# ict_to_hid.net
KiCad netlist of a schematic drawn in EAGLE
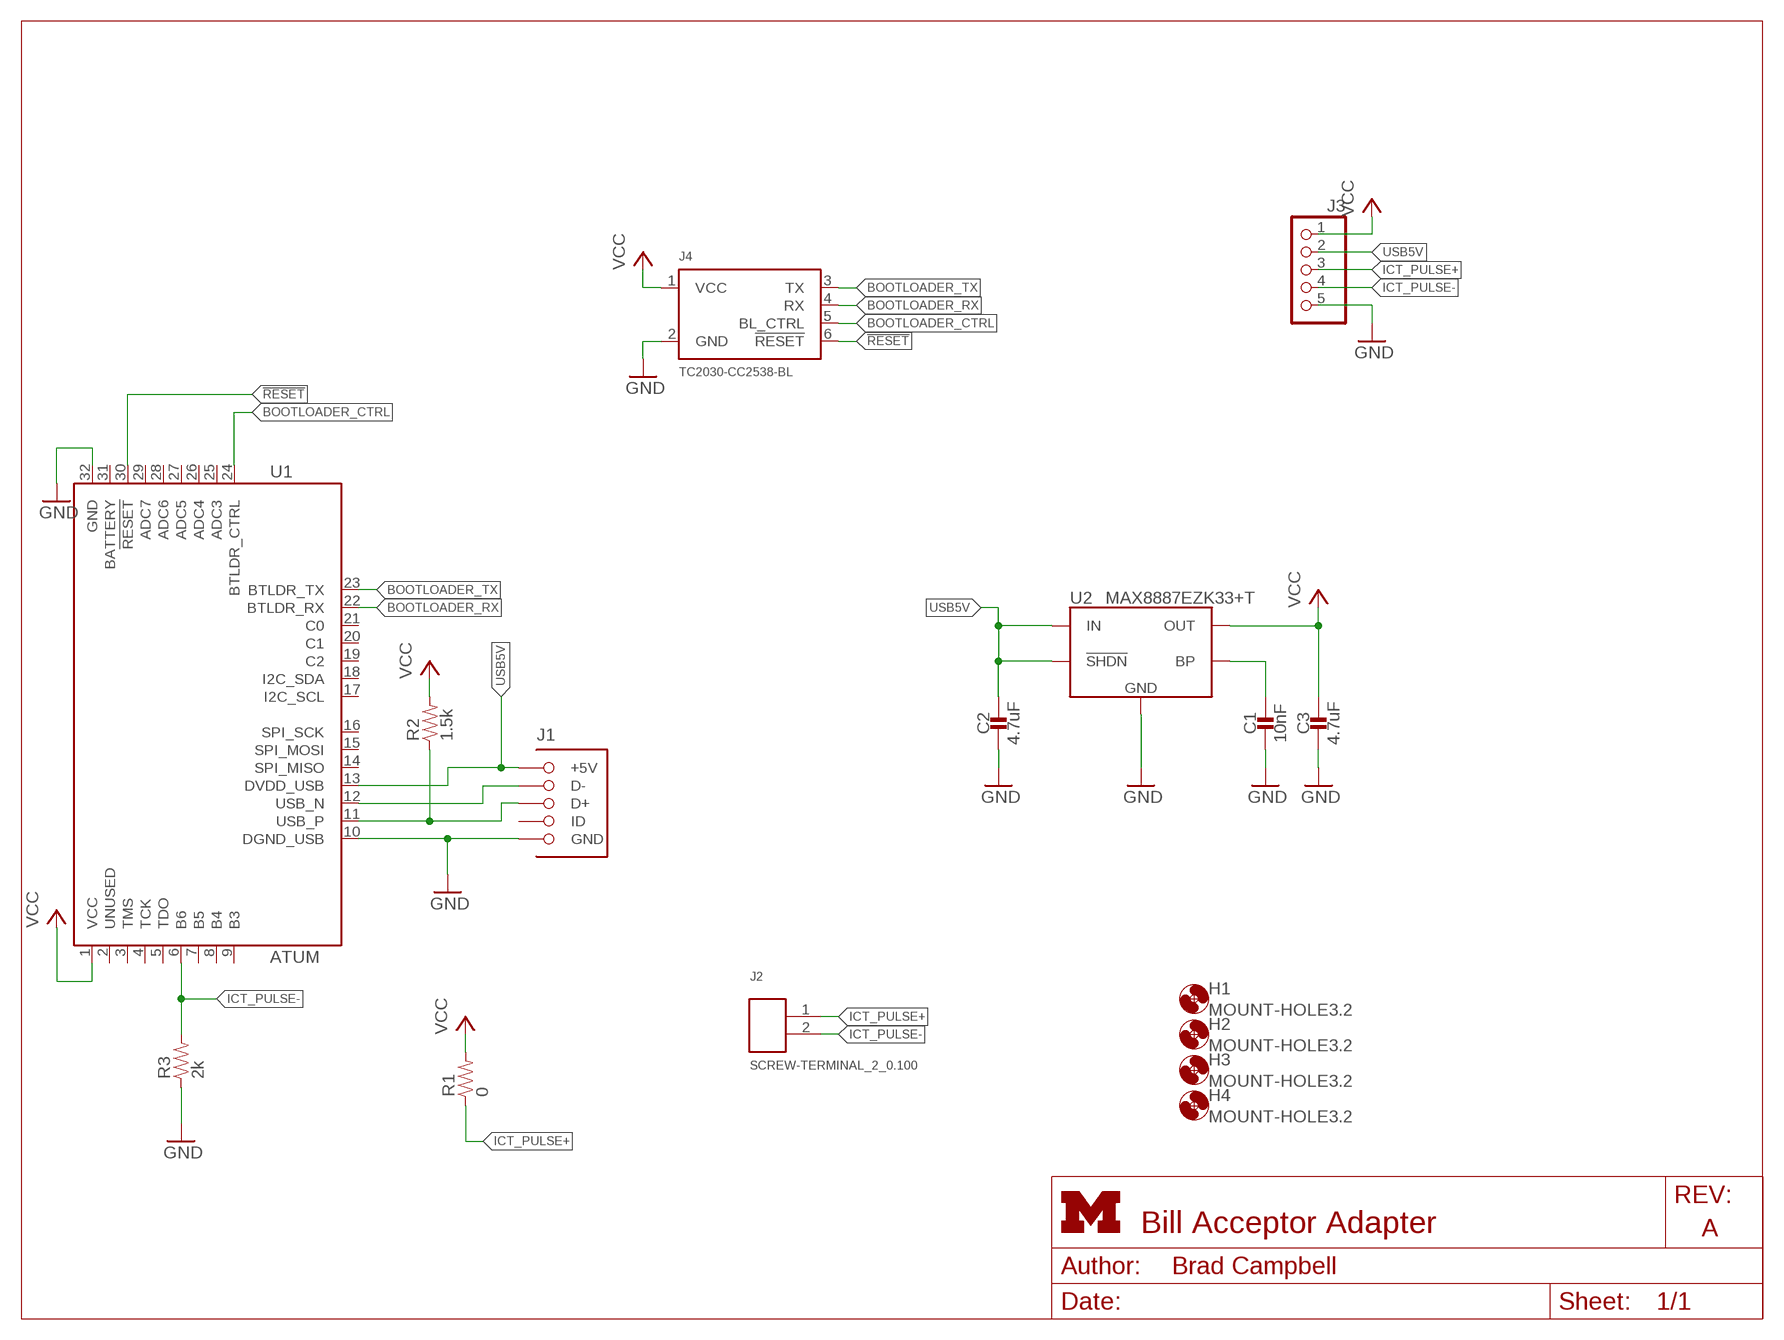
[diagram p0: schematic, sheet 1]

(export (version "E")
  (design (tool "Eeschema 10.0.6"))
  (components
    (comp (ref "C1")
      (value "10nF")
      (footprint "eagle-import:0603_CAP")
      (libsource (lib "eagle-import") (part "CAPACITOR0603_CAP"))
    )
    (comp (ref "C2")
      (value "4.7uF")
      (footprint "eagle-import:0603_CAP")
      (libsource (lib "eagle-import") (part "CAPACITOR0603_CAP"))
    )
    (comp (ref "C3")
      (value "4.7uF")
      (footprint "eagle-import:0603_CAP")
      (libsource (lib "eagle-import") (part "CAPACITOR0603_CAP"))
    )
    (comp (ref "H1")
      (value "MOUNT-HOLE3.2")
      (footprint "eagle-import:3,2")
      (libsource (lib "eagle-import") (part "MOUNT-HOLE3.2"))
    )
    (comp (ref "H2")
      (value "MOUNT-HOLE3.2")
      (footprint "eagle-import:3,2")
      (libsource (lib "eagle-import") (part "MOUNT-HOLE3.2"))
    )
    (comp (ref "H3")
      (value "MOUNT-HOLE3.2")
      (footprint "eagle-import:3,2")
      (libsource (lib "eagle-import") (part "MOUNT-HOLE3.2"))
    )
    (comp (ref "H4")
      (value "MOUNT-HOLE3.2")
      (footprint "eagle-import:3,2")
      (libsource (lib "eagle-import") (part "MOUNT-HOLE3.2"))
    )
    (comp (ref "J1")
      (value "MICRO_USB_B_HIROSE_ZX62R-B-5P")
      (footprint "eagle-import:USB_MICRO_B-HIROSE-ZX62R-B-5P")
      (libsource (lib "eagle-import") (part "MICRO_USB_B_HIROSE_ZX62R-B-5P"))
    )
    (comp (ref "J2")
      (value "SCREW-TERMINAL_2_0.100")
      (footprint "eagle-import:CONN_BLOCK_2")
      (libsource (lib "eagle-import") (part "SCREW-TERMINAL_2_0.100"))
    )
    (comp (ref "J3")
      (value "PINHD-1X5")
      (footprint "eagle-import:1X05")
      (libsource (lib "eagle-import") (part "PINHD-1X5"))
    )
    (comp (ref "J4")
      (value "TC2030-CC2538-BL")
      (footprint "eagle-import:TC2030-IDC")
      (libsource (lib "eagle-import") (part "TC2030-CC2538-BL"))
    )
    (comp (ref "R1")
      (value "0")
      (footprint "eagle-import:0603-RES")
      (libsource (lib "eagle-import") (part "RESISTOR0603_RES"))
    )
    (comp (ref "R2")
      (value "1.5k")
      (footprint "eagle-import:0603-RES")
      (libsource (lib "eagle-import") (part "RESISTOR0603_RES"))
    )
    (comp (ref "R3")
      (value "2k")
      (footprint "eagle-import:0603-RES")
      (libsource (lib "eagle-import") (part "RESISTOR0603_RES"))
    )
    (comp (ref "U1")
      (value "ATUM")
      (footprint "eagle-import:ATUM")
      (libsource (lib "eagle-import") (part "ATUM"))
    )
    (comp (ref "U2")
      (value "MAX8887EZK33+T")
      (footprint "eagle-import:SOT-23-5")
      (libsource (lib "eagle-import") (part "MAX8887EZK33+T"))
    )
  )
  (nets
    (net (code "1") (name "/~{RESET}") (class "Default")
      (node (ref "J4") (pin "6") (pinfunction "~{RESET}_6") (pintype "bidirectional"))
      (node (ref "U1") (pin "30") (pinfunction "~{RESET}_30") (pintype "bidirectional"))
    )
    (net (code "2") (name "BOOTLOADER_CTRL") (class "Default")
      (node (ref "J4") (pin "5") (pinfunction "BL_CTRL_5") (pintype "bidirectional"))
      (node (ref "U1") (pin "24") (pinfunction "BTLDR_CTRL_24") (pintype "bidirectional"))
    )
    (net (code "3") (name "BOOTLOADER_RX") (class "Default")
      (node (ref "J4") (pin "4") (pinfunction "RX_4") (pintype "bidirectional"))
      (node (ref "U1") (pin "22") (pinfunction "BTLDR_RX_22") (pintype "bidirectional"))
    )
    (net (code "4") (name "BOOTLOADER_TX") (class "Default")
      (node (ref "J4") (pin "3") (pinfunction "TX_3") (pintype "bidirectional"))
      (node (ref "U1") (pin "23") (pinfunction "BTLDR_TX_23") (pintype "bidirectional"))
    )
    (net (code "5") (name "GND") (class "Default")
      (node (ref "C1") (pin "2") (pinfunction "2_2") (pintype "bidirectional"))
      (node (ref "C2") (pin "2") (pinfunction "2_2") (pintype "bidirectional"))
      (node (ref "C3") (pin "2") (pinfunction "2_2") (pintype "bidirectional"))
      (node (ref "J1") (pin "5") (pinfunction "GND_5") (pintype "bidirectional"))
      (node (ref "J3") (pin "5") (pinfunction "5_5") (pintype "passive"))
      (node (ref "J4") (pin "2") (pinfunction "GND_2") (pintype "bidirectional"))
      (node (ref "R3") (pin "1") (pinfunction "1_1") (pintype "passive"))
      (node (ref "U1") (pin "10") (pinfunction "DGND_USB_10") (pintype "bidirectional"))
      (node (ref "U1") (pin "32") (pinfunction "GND_32") (pintype "bidirectional"))
      (node (ref "U2") (pin "2") (pinfunction "GND_2") (pintype "bidirectional"))
    )
    (net (code "6") (name "ICT_PULSE+") (class "Default")
      (node (ref "J2") (pin "1") (pinfunction "1_1") (pintype "bidirectional"))
      (node (ref "J3") (pin "3") (pinfunction "3_3") (pintype "passive"))
      (node (ref "R1") (pin "1") (pinfunction "1_1") (pintype "passive"))
    )
    (net (code "7") (name "ICT_PULSE-") (class "Default")
      (node (ref "J2") (pin "2") (pinfunction "2_2") (pintype "bidirectional"))
      (node (ref "J3") (pin "4") (pinfunction "4_4") (pintype "passive"))
      (node (ref "R3") (pin "2") (pinfunction "2_2") (pintype "passive"))
      (node (ref "U1") (pin "6") (pinfunction "B6_6") (pintype "bidirectional"))
    )
    (net (code "8") (name "Net-(J1-D+)") (class "Default")
      (node (ref "J1") (pin "3") (pinfunction "D+_3") (pintype "bidirectional"))
      (node (ref "R2") (pin "1") (pinfunction "1_1") (pintype "passive"))
      (node (ref "U1") (pin "11") (pinfunction "USB_P_11") (pintype "bidirectional"))
    )
    (net (code "9") (name "Net-(J1-D-)") (class "Default")
      (node (ref "J1") (pin "2") (pinfunction "D-_2") (pintype "bidirectional"))
      (node (ref "U1") (pin "12") (pinfunction "USB_N_12") (pintype "bidirectional"))
    )
    (net (code "10") (name "Net-(U2-BP)") (class "Default")
      (node (ref "C1") (pin "1") (pinfunction "1_1") (pintype "bidirectional"))
      (node (ref "U2") (pin "4") (pinfunction "BP_4") (pintype "bidirectional"))
    )
    (net (code "11") (name "USB5V") (class "Default")
      (node (ref "C2") (pin "1") (pinfunction "1_1") (pintype "bidirectional"))
      (node (ref "J1") (pin "1") (pinfunction "+5V_1") (pintype "bidirectional"))
      (node (ref "J3") (pin "2") (pinfunction "2_2") (pintype "passive"))
      (node (ref "U1") (pin "13") (pinfunction "DVDD_USB_13") (pintype "bidirectional"))
      (node (ref "U2") (pin "1") (pinfunction "IN_1") (pintype "bidirectional"))
      (node (ref "U2") (pin "3") (pinfunction "~{SHDN}_3") (pintype "bidirectional"))
    )
    (net (code "12") (name "VCC") (class "Default")
      (node (ref "C3") (pin "1") (pinfunction "1_1") (pintype "bidirectional"))
      (node (ref "J3") (pin "1") (pinfunction "1_1") (pintype "passive"))
      (node (ref "J4") (pin "1") (pinfunction "VCC_1") (pintype "bidirectional"))
      (node (ref "R1") (pin "2") (pinfunction "2_2") (pintype "passive"))
      (node (ref "R2") (pin "2") (pinfunction "2_2") (pintype "passive"))
      (node (ref "U1") (pin "1") (pinfunction "VCC_1") (pintype "bidirectional"))
      (node (ref "U2") (pin "5") (pinfunction "OUT_5") (pintype "bidirectional"))
    )
    (net (code "13") (name "unconnected-(J1-ID-Pad4)") (class "Default")
      (node (ref "J1") (pin "4") (pinfunction "ID_4") (pintype "bidirectional"))
    )
    (net (code "14") (name "unconnected-(U1-ADC3-Pad25)") (class "Default")
      (node (ref "U1") (pin "25") (pinfunction "ADC3_25") (pintype "bidirectional"))
    )
    (net (code "15") (name "unconnected-(U1-ADC4-Pad26)") (class "Default")
      (node (ref "U1") (pin "26") (pinfunction "ADC4_26") (pintype "bidirectional"))
    )
    (net (code "16") (name "unconnected-(U1-ADC5-Pad27)") (class "Default")
      (node (ref "U1") (pin "27") (pinfunction "ADC5_27") (pintype "bidirectional"))
    )
    (net (code "17") (name "unconnected-(U1-ADC6-Pad28)") (class "Default")
      (node (ref "U1") (pin "28") (pinfunction "ADC6_28") (pintype "bidirectional"))
    )
    (net (code "18") (name "unconnected-(U1-ADC7-Pad29)") (class "Default")
      (node (ref "U1") (pin "29") (pinfunction "ADC7_29") (pintype "bidirectional"))
    )
    (net (code "19") (name "unconnected-(U1-B3-Pad9)") (class "Default")
      (node (ref "U1") (pin "9") (pinfunction "B3_9") (pintype "bidirectional"))
    )
    (net (code "20") (name "unconnected-(U1-B4-Pad8)") (class "Default")
      (node (ref "U1") (pin "8") (pinfunction "B4_8") (pintype "bidirectional"))
    )
    (net (code "21") (name "unconnected-(U1-B5-Pad7)") (class "Default")
      (node (ref "U1") (pin "7") (pinfunction "B5_7") (pintype "bidirectional"))
    )
    (net (code "22") (name "unconnected-(U1-BATTERY-Pad31)") (class "Default")
      (node (ref "U1") (pin "31") (pinfunction "BATTERY_31") (pintype "bidirectional"))
    )
    (net (code "23") (name "unconnected-(U1-C0-Pad21)") (class "Default")
      (node (ref "U1") (pin "21") (pinfunction "C0_21") (pintype "bidirectional"))
    )
    (net (code "24") (name "unconnected-(U1-C1-Pad20)") (class "Default")
      (node (ref "U1") (pin "20") (pinfunction "C1_20") (pintype "bidirectional"))
    )
    (net (code "25") (name "unconnected-(U1-C2-Pad19)") (class "Default")
      (node (ref "U1") (pin "19") (pinfunction "C2_19") (pintype "bidirectional"))
    )
    (net (code "26") (name "unconnected-(U1-I2C_SCL-Pad17)") (class "Default")
      (node (ref "U1") (pin "17") (pinfunction "I2C_SCL_17") (pintype "bidirectional"))
    )
    (net (code "27") (name "unconnected-(U1-I2C_SDA-Pad18)") (class "Default")
      (node (ref "U1") (pin "18") (pinfunction "I2C_SDA_18") (pintype "bidirectional"))
    )
    (net (code "28") (name "unconnected-(U1-SPI_MISO-Pad14)") (class "Default")
      (node (ref "U1") (pin "14") (pinfunction "SPI_MISO_14") (pintype "bidirectional"))
    )
    (net (code "29") (name "unconnected-(U1-SPI_MOSI-Pad15)") (class "Default")
      (node (ref "U1") (pin "15") (pinfunction "SPI_MOSI_15") (pintype "bidirectional"))
    )
    (net (code "30") (name "unconnected-(U1-SPI_SCK-Pad16)") (class "Default")
      (node (ref "U1") (pin "16") (pinfunction "SPI_SCK_16") (pintype "bidirectional"))
    )
    (net (code "31") (name "unconnected-(U1-TCK-Pad4)") (class "Default")
      (node (ref "U1") (pin "4") (pinfunction "TCK_4") (pintype "bidirectional"))
    )
    (net (code "32") (name "unconnected-(U1-TDO-Pad5)") (class "Default")
      (node (ref "U1") (pin "5") (pinfunction "TDO_5") (pintype "bidirectional"))
    )
    (net (code "33") (name "unconnected-(U1-TMS-Pad3)") (class "Default")
      (node (ref "U1") (pin "3") (pinfunction "TMS_3") (pintype "bidirectional"))
    )
    (net (code "34") (name "unconnected-(U1-UNUSED-Pad2)") (class "Default")
      (node (ref "U1") (pin "2") (pinfunction "UNUSED_2") (pintype "bidirectional"))
    )
  )
)
